# Photo.net
KiCad netlist of a schematic drawn in Altium Designer
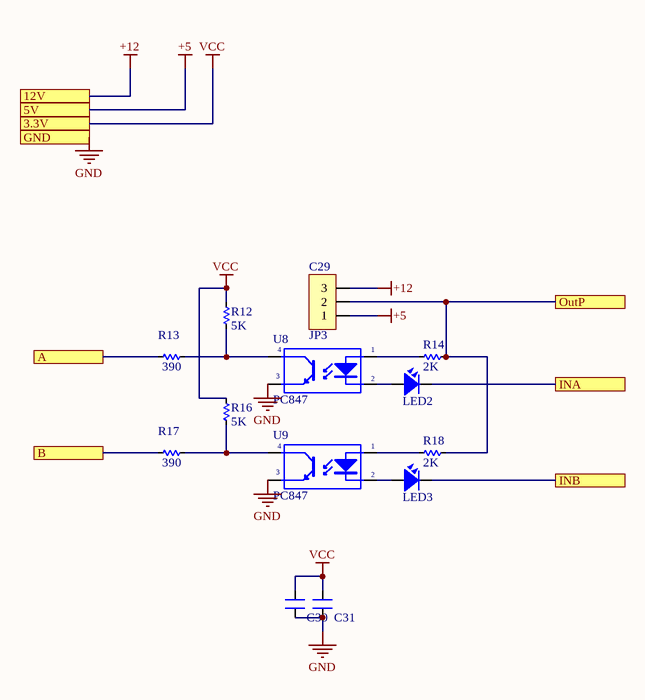
[diagram p0: Photo.SchDoc]

(export (version "E")
  (design (tool "Eeschema 10.0.6"))
  (components
    (comp (ref "C29")
      (value "JP3")
      (footprint "JP3-C1T")
      (description "WR-PHD 2.54 mm Angled Socket Header")
      (fields
        (field (name "MANUFACTURER") "Würth Elektronik eiSos GmbH")
        (field (name "PARTNO") "613003143121")
        (field (name "CREATED BY") "Karrer Zheng")
      )
      (libsource (lib "nhan") (part "JP3"))
    )
    (comp (ref "C30") (value "100nF") (footprint "CN-SMD-0603_big") (libsource (lib "nhan") (part "CN")))
    (comp (ref "C31") (value "100nF") (footprint "CN-SMD-0603_big") (libsource (lib "nhan") (part "CN")))
    (comp (ref "LED2")
      (value "LED")
      (footprint "LED-0805-Green")
      (libsource (lib "BanLinhKien") (part "LED SMD"))
    )
    (comp (ref "LED3")
      (value "LED")
      (footprint "LED-0805-Green")
      (libsource (lib "BanLinhKien") (part "LED SMD"))
    )
    (comp (ref "R12") (value "5K") (footprint "RES-SMD-0603_BIG") (libsource (lib "nhan") (part "R")))
    (comp (ref "R13") (value "390") (footprint "RES-SMD-0603_BIG") (libsource (lib "nhan") (part "R")))
    (comp (ref "R14") (value "2K") (footprint "RES-SMD-0603_BIG") (libsource (lib "nhan") (part "R")))
    (comp (ref "R16") (value "5K") (footprint "RES-SMD-0603_BIG") (libsource (lib "nhan") (part "R")))
    (comp (ref "R17") (value "390") (footprint "RES-SMD-0603_BIG") (libsource (lib "nhan") (part "R")))
    (comp (ref "R18") (value "2K") (footprint "RES-SMD-0603_BIG") (libsource (lib "nhan") (part "R")))
    (comp (ref "U8")
      (value "PC847")
      (footprint "DIP4")
      (description "Single Opto")
      (libsource (lib "BanLinhKien") (part "PC817"))
    )
    (comp (ref "U9")
      (value "PC847")
      (footprint "DIP4")
      (description "Single Opto")
      (libsource (lib "BanLinhKien") (part "PC817"))
    )
  )
  (nets
    (net (code "1") (name "+5") (class "Default")
      (node (ref "C29") (pin "1") (pinfunction "1_1") (pintype "passive"))
    )
    (net (code "2") (name "+12") (class "Default")
      (node (ref "C29") (pin "3") (pinfunction "3_3") (pintype "passive"))
    )
    (net (code "3") (name "/A") (class "Default")
      (node (ref "R13") (pin "1") (pinfunction "1_1") (pintype "passive"))
    )
    (net (code "4") (name "/B") (class "Default")
      (node (ref "R17") (pin "1") (pinfunction "1_1") (pintype "passive"))
    )
    (net (code "5") (name "/INA") (class "Default")
      (node (ref "LED2") (pin "2") (pinfunction "2_2") (pintype "passive"))
    )
    (net (code "6") (name "/INB") (class "Default")
      (node (ref "LED3") (pin "2") (pinfunction "2_2") (pintype "passive"))
    )
    (net (code "7") (name "/OutP") (class "Default")
      (node (ref "C29") (pin "2") (pinfunction "2_2") (pintype "passive"))
      (node (ref "R14") (pin "1") (pinfunction "1_1") (pintype "passive"))
      (node (ref "R18") (pin "1") (pinfunction "1_1") (pintype "passive"))
    )
    (net (code "8") (name "GND") (class "Default")
      (node (ref "C30") (pin "1") (pinfunction "1_1") (pintype "passive"))
      (node (ref "C31") (pin "1") (pinfunction "1_1") (pintype "passive"))
      (node (ref "U8") (pin "3") (pinfunction "E_3") (pintype "passive"))
      (node (ref "U9") (pin "3") (pinfunction "E_3") (pintype "passive"))
    )
    (net (code "9") (name "Net-(U8-A)") (class "Default")
      (node (ref "R14") (pin "2") (pinfunction "2_2") (pintype "passive"))
      (node (ref "U8") (pin "1") (pinfunction "A_1") (pintype "passive"))
    )
    (net (code "10") (name "Net-(U8-C)") (class "Default")
      (node (ref "R12") (pin "2") (pinfunction "2_2") (pintype "passive"))
      (node (ref "R13") (pin "2") (pinfunction "2_2") (pintype "passive"))
      (node (ref "U8") (pin "4") (pinfunction "C_4") (pintype "passive"))
    )
    (net (code "11") (name "Net-(U8-K)") (class "Default")
      (node (ref "LED2") (pin "1") (pinfunction "1_1") (pintype "passive"))
      (node (ref "U8") (pin "2") (pinfunction "K_2") (pintype "passive"))
    )
    (net (code "12") (name "Net-(U9-A)") (class "Default")
      (node (ref "R18") (pin "2") (pinfunction "2_2") (pintype "passive"))
      (node (ref "U9") (pin "1") (pinfunction "A_1") (pintype "passive"))
    )
    (net (code "13") (name "Net-(U9-C)") (class "Default")
      (node (ref "R16") (pin "2") (pinfunction "2_2") (pintype "passive"))
      (node (ref "R17") (pin "2") (pinfunction "2_2") (pintype "passive"))
      (node (ref "U9") (pin "4") (pinfunction "C_4") (pintype "passive"))
    )
    (net (code "14") (name "Net-(U9-K)") (class "Default")
      (node (ref "LED3") (pin "1") (pinfunction "1_1") (pintype "passive"))
      (node (ref "U9") (pin "2") (pinfunction "K_2") (pintype "passive"))
    )
    (net (code "15") (name "VCC") (class "Default")
      (node (ref "C30") (pin "2") (pinfunction "2_2") (pintype "passive"))
      (node (ref "C31") (pin "2") (pinfunction "2_2") (pintype "passive"))
      (node (ref "R12") (pin "1") (pinfunction "1_1") (pintype "passive"))
      (node (ref "R16") (pin "1") (pinfunction "1_1") (pintype "passive"))
    )
  )
)
